# zulu_a7_2.net
KiCad netlist of a schematic drawn in Altium Designer
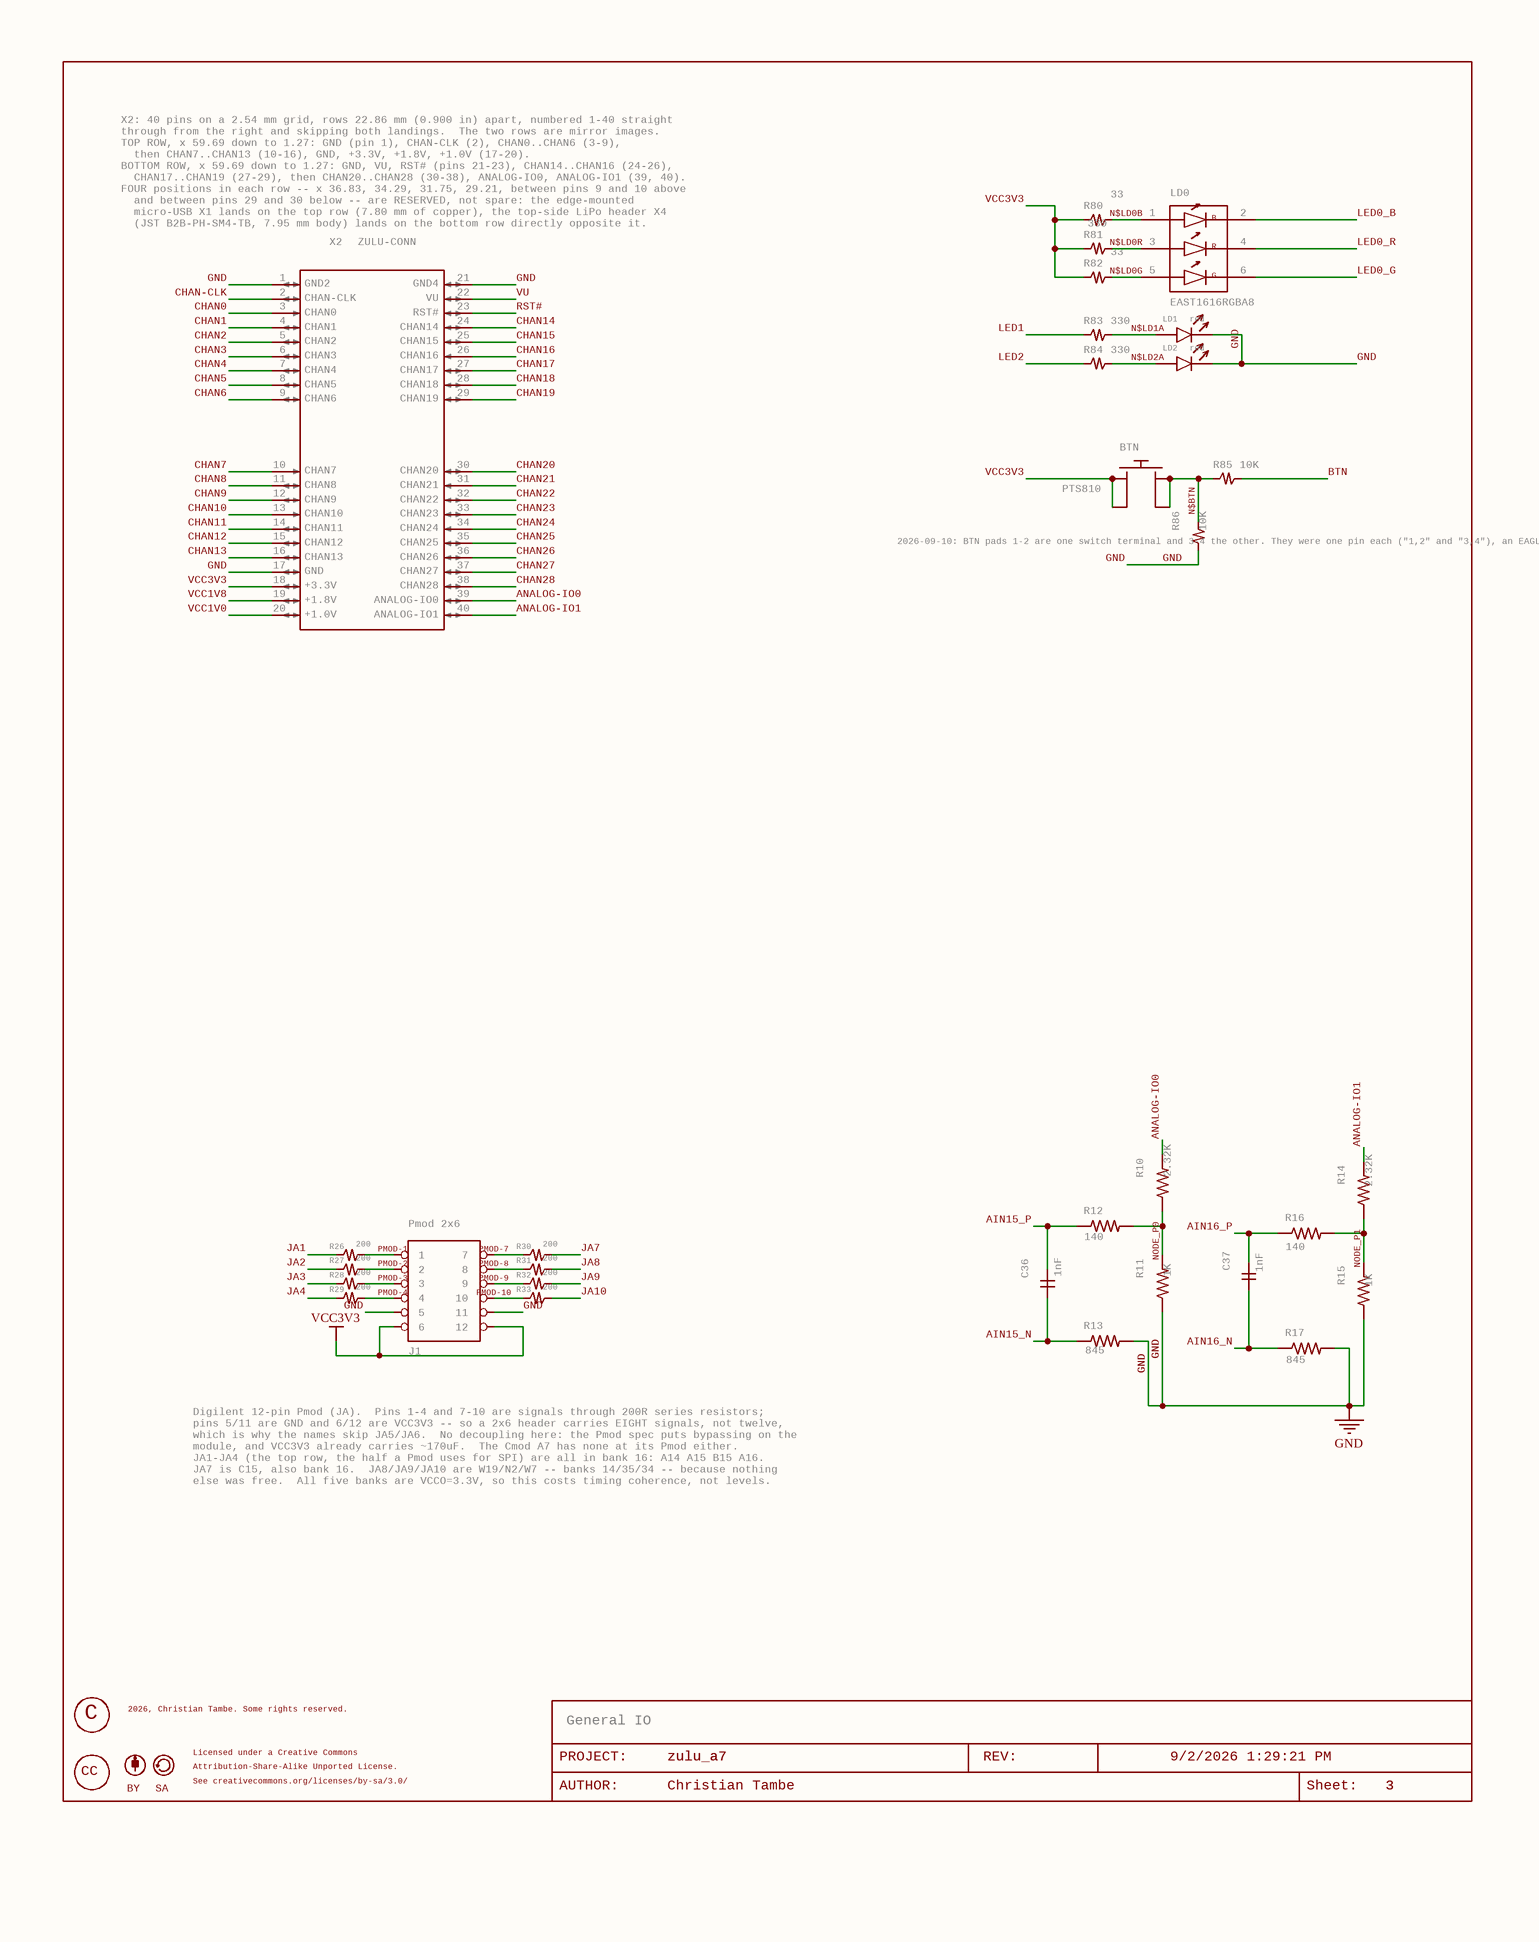
[diagram p0: zulu_a7_2.SchDoc]

(export (version "E")
  (design (tool "Eeschema 10.0.6"))
  (components
    (comp (ref "BTN")
      (value "PTS810")
      (footprint "PTS810")
      (fields (field (name "MANF") "Littelfuse (C&K)") (field (name "LIBRARYNAME") "ctambe"))
      (libsource (lib "ctambe") (part "SWITCH_TACT"))
    )
    (comp (ref "C36")
      (value "1nF")
      (footprint "C0402")
      (description "CAPACITOR, generic non-polarized, horizontal pins")
      (fields (field (name "MANF") "Murata"))
      (libsource (lib "rcl") (part "C-GENERICC0402"))
    )
    (comp (ref "C37")
      (value "1nF")
      (footprint "C0402")
      (description "CAPACITOR, generic non-polarized, horizontal pins")
      (fields (field (name "MANF") "Murata"))
      (libsource (lib "rcl") (part "C-GENERICC0402"))
    )
    (comp (ref "FRAME3")
      (value "DOCFIELD")
      (description "DOCUMENT FIELD")
      (fields
        (field (name "LAST_DATE_TIME") "9/2/2026 1:29:21 PM")
        (field (name "SHEET") "Sheet:")
        (field (name "SHEET_1") "3")
        (field (name "REV") "REV:")
        (field (name "PROJECT") "PROJECT:")
        (field (name "DRAWING_NAME") "zulu_a7")
        (field (name "AUTHOR") "Christian Tambe")
        (field (name "DRAWING_NAME_1") "zulu_a7")
        (field (name "SHEET_2") "3")
        (field (name "LIBRARYNAME") "ctambe")
      )
      (libsource (lib "ctambe") (part "DOCFIELD"))
    )
    (comp (ref "J1")
      (value "Pmod 2x6")
      (footprint "2X06")
      (fields (field (name "MANF") "Sullins") (field (name "LIBRARYNAME") "ctambe"))
      (libsource (lib "ctambe") (part "PINHD-2X6"))
    )
    (comp (ref "LD0")
      (value "EAST1616RGBA8")
      (footprint "EVERLIGHT-19-337")
      (fields
        (field (name "B") "B")
        (field (name "R") "R")
        (field (name "G") "G")
        (field (name "MANF") "Everlight")
        (field (name "LIBRARYNAME") "ctambe")
      )
      (libsource (lib "ctambe") (part "LED_RGB"))
    )
    (comp (ref "LD1")
      (value "red")
      (footprint "LED0603")
      (description "LED")
      (fields (field (name "MANF") "Lite-On") (field (name "LIBRARYNAME") "ctambe"))
      (libsource (lib "ctambe") (part "LED"))
    )
    (comp (ref "LD2")
      (value "red")
      (footprint "LED0603")
      (description "LED")
      (fields (field (name "MANF") "Lite-On") (field (name "LIBRARYNAME") "ctambe"))
      (libsource (lib "ctambe") (part "LED"))
    )
    (comp (ref "R10")
      (value "2.32K")
      (footprint "R0201")
      (description "RESISTOR, American symbol")
      (fields (field (name "MANF") "Yageo"))
      (libsource (lib "rcl") (part "R-US_R0201"))
    )
    (comp (ref "R11")
      (value "1K")
      (footprint "R0201")
      (description "RESISTOR, American symbol")
      (fields (field (name "MANF") "Yageo"))
      (libsource (lib "rcl") (part "R-US_R0201"))
    )
    (comp (ref "R12")
      (value "140")
      (footprint "R0201")
      (description "RESISTOR, American symbol")
      (fields (field (name "MANF") "Yageo"))
      (libsource (lib "rcl") (part "R-US_R0201"))
    )
    (comp (ref "R13")
      (value "845")
      (footprint "R0201")
      (description "RESISTOR, American symbol")
      (fields (field (name "MANF") "Yageo"))
      (libsource (lib "rcl") (part "R-US_R0201"))
    )
    (comp (ref "R14")
      (value "2.32K")
      (footprint "R0201")
      (description "RESISTOR, American symbol")
      (fields (field (name "MANF") "Yageo"))
      (libsource (lib "rcl") (part "R-US_R0201"))
    )
    (comp (ref "R15")
      (value "1K")
      (footprint "R0201")
      (description "RESISTOR, American symbol")
      (fields (field (name "MANF") "Yageo"))
      (libsource (lib "rcl") (part "R-US_R0201"))
    )
    (comp (ref "R16")
      (value "140")
      (footprint "R0201")
      (description "RESISTOR, American symbol")
      (fields (field (name "MANF") "Yageo"))
      (libsource (lib "rcl") (part "R-US_R0201"))
    )
    (comp (ref "R17")
      (value "845")
      (footprint "R0201")
      (description "RESISTOR, American symbol")
      (fields (field (name "MANF") "Yageo"))
      (libsource (lib "rcl") (part "R-US_R0201"))
    )
    (comp (ref "R26")
      (value "200")
      (footprint "R0201")
      (description "RESISTOR, American symbol, small 2-zigzag variant (sheet 2 only)")
      (fields (field (name "MANF") "Yageo"))
      (libsource (lib "rcl") (part "R-US_SMALLR0201"))
    )
    (comp (ref "R27")
      (value "200")
      (footprint "R0201")
      (description "RESISTOR, American symbol, small 2-zigzag variant (sheet 2 only)")
      (fields (field (name "MANF") "Yageo"))
      (libsource (lib "rcl") (part "R-US_SMALLR0201"))
    )
    (comp (ref "R28")
      (value "200")
      (footprint "R0201")
      (description "RESISTOR, American symbol, small 2-zigzag variant (sheet 2 only)")
      (fields (field (name "MANF") "Yageo"))
      (libsource (lib "rcl") (part "R-US_SMALLR0201"))
    )
    (comp (ref "R29")
      (value "200")
      (footprint "R0201")
      (description "RESISTOR, American symbol, small 2-zigzag variant (sheet 2 only)")
      (fields (field (name "MANF") "Yageo"))
      (libsource (lib "rcl") (part "R-US_SMALLR0201"))
    )
    (comp (ref "R30")
      (value "200")
      (footprint "R0201")
      (description "RESISTOR, American symbol, small 2-zigzag variant (sheet 2 only)")
      (fields (field (name "MANF") "Yageo"))
      (libsource (lib "rcl") (part "R-US_SMALLR0201"))
    )
    (comp (ref "R31")
      (value "200")
      (footprint "R0201")
      (description "RESISTOR, American symbol, small 2-zigzag variant (sheet 2 only)")
      (fields (field (name "MANF") "Yageo"))
      (libsource (lib "rcl") (part "R-US_SMALLR0201"))
    )
    (comp (ref "R32")
      (value "200")
      (footprint "R0201")
      (description "RESISTOR, American symbol, small 2-zigzag variant (sheet 2 only)")
      (fields (field (name "MANF") "Yageo"))
      (libsource (lib "rcl") (part "R-US_SMALLR0201"))
    )
    (comp (ref "R33")
      (value "200")
      (footprint "R0201")
      (description "RESISTOR, American symbol, small 2-zigzag variant (sheet 2 only)")
      (fields (field (name "MANF") "Yageo"))
      (libsource (lib "rcl") (part "R-US_SMALLR0201"))
    )
    (comp (ref "R80")
      (value "33")
      (footprint "R0402")
      (description "RESISTOR, American symbol, small 2-zigzag variant (sheet 2 only)")
      (fields (field (name "MANF") "Yageo"))
      (libsource (lib "rcl") (part "R-US_SMALLR0402"))
    )
    (comp (ref "R81")
      (value "330")
      (footprint "R0402")
      (description "RESISTOR, American symbol, small 2-zigzag variant (sheet 2 only)")
      (fields (field (name "MANF") "Yageo"))
      (libsource (lib "rcl") (part "R-US_SMALLR0402"))
    )
    (comp (ref "R82")
      (value "33")
      (footprint "R0402")
      (description "RESISTOR, American symbol, small 2-zigzag variant (sheet 2 only)")
      (fields (field (name "MANF") "Yageo"))
      (libsource (lib "rcl") (part "R-US_SMALLR0402"))
    )
    (comp (ref "R83")
      (value "330")
      (footprint "R0402")
      (description "RESISTOR, American symbol, small 2-zigzag variant (sheet 2 only)")
      (fields (field (name "MANF") "Yageo"))
      (libsource (lib "rcl") (part "R-US_SMALLR0402"))
    )
    (comp (ref "R84")
      (value "330")
      (footprint "R0402")
      (description "RESISTOR, American symbol, small 2-zigzag variant (sheet 2 only)")
      (fields (field (name "MANF") "Yageo"))
      (libsource (lib "rcl") (part "R-US_SMALLR0402"))
    )
    (comp (ref "R85")
      (value "10K")
      (footprint "R0402")
      (description "RESISTOR, American symbol, small 2-zigzag variant (sheet 2 only)")
      (fields (field (name "MANF") "Yageo"))
      (libsource (lib "rcl") (part "R-US_SMALLR0402"))
    )
    (comp (ref "R86")
      (value "10K")
      (footprint "R0402")
      (description "RESISTOR, American symbol, small 2-zigzag variant (sheet 2 only)")
      (fields (field (name "MANF") "Yageo"))
      (libsource (lib "rcl") (part "R-US_SMALLR0402"))
    )
    (comp (ref "U$2")
      (value "CC_CC")
      (footprint "CC_CC")
      (fields (field (name "CC") "CC") (field (name "LIBRARYNAME") "ctambe"))
      (libsource (lib "ctambe") (part "CC_CC"))
    )
    (comp (ref "U$3")
      (value "CC_BY")
      (footprint "CC_BY")
      (fields (field (name "BY") "BY") (field (name "LIBRARYNAME") "ctambe"))
      (libsource (lib "ctambe") (part "CC_BY"))
    )
    (comp (ref "U$4")
      (value "CC_SA")
      (footprint "CC_SA")
      (fields (field (name "SA") "SA") (field (name "LIBRARYNAME") "ctambe"))
      (libsource (lib "ctambe") (part "CC_SA"))
    )
    (comp (ref "U$5")
      (value "CC_COPYRIGHT")
      (footprint "CC_COPYRIGHT")
      (fields (field (name "C") "C") (field (name "LIBRARYNAME") "ctambe"))
      (libsource (lib "ctambe") (part "CC_COPYRIGHT"))
    )
    (comp (ref "X2")
      (value "ZULU-CONN")
      (footprint "ZULU-DIP37")
      (description "Zulu A7 Board Connector")
      (fields
        (field (name "MANF") "Sullins")
        (field (name "GATE") "CHAN-CLK")
        (field (name "PART") "X2")
        (field (name "LIBRARYNAME") "ctambe")
      )
      (libsource (lib "ctambe") (part "ZULU-CONN"))
    )
  )
  (nets
    (net (code "1") (name "/AIN15_N") (class "Default")
      (node (ref "C36") (pin "1") (pinfunction "1_1") (pintype "passive"))
      (node (ref "R13") (pin "1") (pinfunction "1_1") (pintype "passive"))
    )
    (net (code "2") (name "/AIN15_P") (class "Default")
      (node (ref "C36") (pin "2") (pinfunction "2_2") (pintype "passive"))
      (node (ref "R12") (pin "1") (pinfunction "1_1") (pintype "passive"))
    )
    (net (code "3") (name "/AIN16_N") (class "Default")
      (node (ref "C37") (pin "1") (pinfunction "1_1") (pintype "passive"))
      (node (ref "R17") (pin "1") (pinfunction "1_1") (pintype "passive"))
    )
    (net (code "4") (name "/AIN16_P") (class "Default")
      (node (ref "C37") (pin "2") (pinfunction "2_2") (pintype "passive"))
      (node (ref "R16") (pin "1") (pinfunction "1_1") (pintype "passive"))
    )
    (net (code "5") (name "/ANALOG-IO0") (class "Default")
      (node (ref "R10") (pin "2") (pinfunction "2_2") (pintype "passive"))
      (node (ref "X2") (pin "39") (pinfunction "1_39") (pintype "bidirectional"))
    )
    (net (code "6") (name "/ANALOG-IO1") (class "Default")
      (node (ref "R14") (pin "2") (pinfunction "2_2") (pintype "passive"))
      (node (ref "X2") (pin "40") (pinfunction "1_40") (pintype "bidirectional"))
    )
    (net (code "7") (name "/BTN") (class "Default")
      (node (ref "R85") (pin "2") (pinfunction "2_2") (pintype "passive"))
    )
    (net (code "8") (name "/CHAN-CLK") (class "Default")
      (node (ref "X2") (pin "2") (pinfunction "1_2") (pintype "bidirectional"))
    )
    (net (code "9") (name "/CHAN0") (class "Default")
      (node (ref "X2") (pin "3") (pinfunction "1_3") (pintype "input"))
    )
    (net (code "10") (name "/CHAN1") (class "Default")
      (node (ref "X2") (pin "4") (pinfunction "1_4") (pintype "bidirectional"))
    )
    (net (code "11") (name "/CHAN2") (class "Default")
      (node (ref "X2") (pin "5") (pinfunction "1_5") (pintype "bidirectional"))
    )
    (net (code "12") (name "/CHAN3") (class "Default")
      (node (ref "X2") (pin "6") (pinfunction "1_6") (pintype "bidirectional"))
    )
    (net (code "13") (name "/CHAN4") (class "Default")
      (node (ref "X2") (pin "7") (pinfunction "1_7") (pintype "bidirectional"))
    )
    (net (code "14") (name "/CHAN5") (class "Default")
      (node (ref "X2") (pin "8") (pinfunction "1_8") (pintype "bidirectional"))
    )
    (net (code "15") (name "/CHAN6") (class "Default")
      (node (ref "X2") (pin "9") (pinfunction "1_9") (pintype "bidirectional"))
    )
    (net (code "16") (name "/CHAN7") (class "Default")
      (node (ref "X2") (pin "10") (pinfunction "1_10") (pintype "input"))
    )
    (net (code "17") (name "/CHAN8") (class "Default")
      (node (ref "X2") (pin "11") (pinfunction "1_11") (pintype "passive"))
    )
    (net (code "18") (name "/CHAN9") (class "Default")
      (node (ref "X2") (pin "12") (pinfunction "1_12") (pintype "bidirectional"))
    )
    (net (code "19") (name "/CHAN10") (class "Default")
      (node (ref "X2") (pin "13") (pinfunction "1_13") (pintype "input"))
    )
    (net (code "20") (name "/CHAN11") (class "Default")
      (node (ref "X2") (pin "14") (pinfunction "1_14") (pintype "bidirectional"))
    )
    (net (code "21") (name "/CHAN12") (class "Default")
      (node (ref "X2") (pin "15") (pinfunction "1_15") (pintype "bidirectional"))
    )
    (net (code "22") (name "/CHAN13") (class "Default")
      (node (ref "X2") (pin "16") (pinfunction "1_16") (pintype "bidirectional"))
    )
    (net (code "23") (name "/CHAN14") (class "Default")
      (node (ref "X2") (pin "24") (pinfunction "1_24") (pintype "bidirectional"))
    )
    (net (code "24") (name "/CHAN15") (class "Default")
      (node (ref "X2") (pin "25") (pinfunction "1_25") (pintype "bidirectional"))
    )
    (net (code "25") (name "/CHAN16") (class "Default")
      (node (ref "X2") (pin "26") (pinfunction "1_26") (pintype "input"))
    )
    (net (code "26") (name "/CHAN17") (class "Default")
      (node (ref "X2") (pin "27") (pinfunction "1_27") (pintype "bidirectional"))
    )
    (net (code "27") (name "/CHAN18") (class "Default")
      (node (ref "X2") (pin "28") (pinfunction "1_28") (pintype "bidirectional"))
    )
    (net (code "28") (name "/CHAN19") (class "Default")
      (node (ref "X2") (pin "29") (pinfunction "1_29") (pintype "bidirectional"))
    )
    (net (code "29") (name "/CHAN20") (class "Default")
      (node (ref "X2") (pin "30") (pinfunction "1_30") (pintype "bidirectional"))
    )
    (net (code "30") (name "/CHAN21") (class "Default")
      (node (ref "X2") (pin "31") (pinfunction "1_31") (pintype "input"))
    )
    (net (code "31") (name "/CHAN22") (class "Default")
      (node (ref "X2") (pin "32") (pinfunction "1_32") (pintype "bidirectional"))
    )
    (net (code "32") (name "/CHAN23") (class "Default")
      (node (ref "X2") (pin "33") (pinfunction "1_33") (pintype "bidirectional"))
    )
    (net (code "33") (name "/CHAN24") (class "Default")
      (node (ref "X2") (pin "34") (pinfunction "1_34") (pintype "input"))
    )
    (net (code "34") (name "/CHAN25") (class "Default")
      (node (ref "X2") (pin "35") (pinfunction "1_35") (pintype "bidirectional"))
    )
    (net (code "35") (name "/CHAN26") (class "Default")
      (node (ref "X2") (pin "36") (pinfunction "1_36") (pintype "bidirectional"))
    )
    (net (code "36") (name "/CHAN27") (class "Default")
      (node (ref "X2") (pin "37") (pinfunction "1_37") (pintype "bidirectional"))
    )
    (net (code "37") (name "/CHAN28") (class "Default")
      (node (ref "X2") (pin "38") (pinfunction "1_38") (pintype "bidirectional"))
    )
    (net (code "38") (name "/JA1") (class "Default")
      (node (ref "R26") (pin "1") (pinfunction "1_1") (pintype "passive"))
    )
    (net (code "39") (name "/JA2") (class "Default")
      (node (ref "R27") (pin "1") (pinfunction "1_1") (pintype "passive"))
    )
    (net (code "40") (name "/JA3") (class "Default")
      (node (ref "R28") (pin "1") (pinfunction "1_1") (pintype "passive"))
    )
    (net (code "41") (name "/JA4") (class "Default")
      (node (ref "R29") (pin "1") (pinfunction "1_1") (pintype "passive"))
    )
    (net (code "42") (name "/JA7") (class "Default")
      (node (ref "R30") (pin "2") (pinfunction "2_2") (pintype "passive"))
    )
    (net (code "43") (name "/JA8") (class "Default")
      (node (ref "R31") (pin "2") (pinfunction "2_2") (pintype "passive"))
    )
    (net (code "44") (name "/JA9") (class "Default")
      (node (ref "R32") (pin "2") (pinfunction "2_2") (pintype "passive"))
    )
    (net (code "45") (name "/JA10") (class "Default")
      (node (ref "R33") (pin "2") (pinfunction "2_2") (pintype "passive"))
    )
    (net (code "46") (name "/LED0_B") (class "Default")
      (node (ref "LD0") (pin "2") (pinfunction "2_2") (pintype "passive"))
    )
    (net (code "47") (name "/LED0_G") (class "Default")
      (node (ref "LD0") (pin "6") (pinfunction "6_6") (pintype "passive"))
    )
    (net (code "48") (name "/LED0_R") (class "Default")
      (node (ref "LD0") (pin "4") (pinfunction "4_4") (pintype "passive"))
    )
    (net (code "49") (name "/LED1") (class "Default")
      (node (ref "R83") (pin "1") (pinfunction "1_1") (pintype "passive"))
    )
    (net (code "50") (name "/LED2") (class "Default")
      (node (ref "R84") (pin "1") (pinfunction "1_1") (pintype "passive"))
    )
    (net (code "51") (name "/N$BTN") (class "Default")
      (node (ref "BTN") (pin "3") (pinfunction "2_3") (pintype "passive"))
      (node (ref "BTN") (pin "4") (pinfunction "2_4") (pintype "passive"))
      (node (ref "R85") (pin "1") (pinfunction "1_1") (pintype "passive"))
      (node (ref "R86") (pin "2") (pinfunction "2_2") (pintype "passive"))
    )
    (net (code "52") (name "/N$LD0B") (class "Default")
      (node (ref "LD0") (pin "1") (pinfunction "1_1") (pintype "passive"))
      (node (ref "R80") (pin "2") (pinfunction "2_2") (pintype "passive"))
    )
    (net (code "53") (name "/N$LD0G") (class "Default")
      (node (ref "LD0") (pin "5") (pinfunction "5_5") (pintype "passive"))
      (node (ref "R82") (pin "2") (pinfunction "2_2") (pintype "passive"))
    )
    (net (code "54") (name "/N$LD0R") (class "Default")
      (node (ref "LD0") (pin "3") (pinfunction "3_3") (pintype "passive"))
      (node (ref "R81") (pin "2") (pinfunction "2_2") (pintype "passive"))
    )
    (net (code "55") (name "/N$LD1A") (class "Default")
      (node (ref "LD1") (pin "A") (pinfunction "A_A") (pintype "passive"))
      (node (ref "R83") (pin "2") (pinfunction "2_2") (pintype "passive"))
    )
    (net (code "56") (name "/N$LD2A") (class "Default")
      (node (ref "LD2") (pin "A") (pinfunction "A_A") (pintype "passive"))
      (node (ref "R84") (pin "2") (pinfunction "2_2") (pintype "passive"))
    )
    (net (code "57") (name "/NODE_P0") (class "Default")
      (node (ref "R10") (pin "1") (pinfunction "1_1") (pintype "passive"))
      (node (ref "R11") (pin "2") (pinfunction "2_2") (pintype "passive"))
      (node (ref "R12") (pin "2") (pinfunction "2_2") (pintype "passive"))
    )
    (net (code "58") (name "/NODE_P1") (class "Default")
      (node (ref "R14") (pin "1") (pinfunction "1_1") (pintype "passive"))
      (node (ref "R15") (pin "2") (pinfunction "2_2") (pintype "passive"))
      (node (ref "R16") (pin "2") (pinfunction "2_2") (pintype "passive"))
    )
    (net (code "59") (name "/PMOD-1") (class "Default")
      (node (ref "J1") (pin "1") (pinfunction "1_1") (pintype "passive"))
      (node (ref "R26") (pin "2") (pinfunction "2_2") (pintype "passive"))
    )
    (net (code "60") (name "/PMOD-2") (class "Default")
      (node (ref "J1") (pin "2") (pinfunction "2_2") (pintype "passive"))
      (node (ref "R27") (pin "2") (pinfunction "2_2") (pintype "passive"))
    )
    (net (code "61") (name "/PMOD-3") (class "Default")
      (node (ref "J1") (pin "3") (pinfunction "3_3") (pintype "passive"))
      (node (ref "R28") (pin "2") (pinfunction "2_2") (pintype "passive"))
    )
    (net (code "62") (name "/PMOD-4") (class "Default")
      (node (ref "J1") (pin "4") (pinfunction "4_4") (pintype "passive"))
      (node (ref "R29") (pin "2") (pinfunction "2_2") (pintype "passive"))
    )
    (net (code "63") (name "/PMOD-7") (class "Default")
      (node (ref "J1") (pin "7") (pinfunction "7_7") (pintype "passive"))
      (node (ref "R30") (pin "1") (pinfunction "1_1") (pintype "passive"))
    )
    (net (code "64") (name "/PMOD-8") (class "Default")
      (node (ref "J1") (pin "8") (pinfunction "8_8") (pintype "passive"))
      (node (ref "R31") (pin "1") (pinfunction "1_1") (pintype "passive"))
    )
    (net (code "65") (name "/PMOD-9") (class "Default")
      (node (ref "J1") (pin "9") (pinfunction "9_9") (pintype "passive"))
      (node (ref "R32") (pin "1") (pinfunction "1_1") (pintype "passive"))
    )
    (net (code "66") (name "/PMOD-10") (class "Default")
      (node (ref "J1") (pin "10") (pinfunction "10_10") (pintype "passive"))
      (node (ref "R33") (pin "1") (pinfunction "1_1") (pintype "passive"))
    )
    (net (code "67") (name "/RST#") (class "Default")
      (node (ref "X2") (pin "23") (pinfunction "1_23") (pintype "bidirectional"))
    )
    (net (code "68") (name "/VCC1V0") (class "Default")
      (node (ref "X2") (pin "20") (pinfunction "1_20") (pintype "bidirectional"))
    )
    (net (code "69") (name "/VCC1V8") (class "Default")
      (node (ref "X2") (pin "19") (pinfunction "1_19") (pintype "bidirectional"))
    )
    (net (code "70") (name "/VU") (class "Default")
      (node (ref "X2") (pin "22") (pinfunction "1_22") (pintype "bidirectional"))
    )
    (net (code "71") (name "GND") (class "Default")
      (node (ref "J1") (pin "11") (pinfunction "11_11") (pintype "passive"))
      (node (ref "J1") (pin "5") (pinfunction "5_5") (pintype "passive"))
      (node (ref "LD1") (pin "K") (pinfunction "K_K") (pintype "passive"))
      (node (ref "LD2") (pin "K") (pinfunction "K_K") (pintype "passive"))
      (node (ref "R11") (pin "1") (pinfunction "1_1") (pintype "passive"))
      (node (ref "R13") (pin "2") (pinfunction "2_2") (pintype "passive"))
      (node (ref "R15") (pin "1") (pinfunction "1_1") (pintype "passive"))
      (node (ref "R17") (pin "2") (pinfunction "2_2") (pintype "passive"))
      (node (ref "R86") (pin "1") (pinfunction "1_1") (pintype "passive"))
      (node (ref "X2") (pin "1") (pinfunction "1_1") (pintype "bidirectional"))
      (node (ref "X2") (pin "17") (pinfunction "1_17") (pintype "bidirectional"))
      (node (ref "X2") (pin "21") (pinfunction "1_21") (pintype "bidirectional"))
    )
    (net (code "72") (name "VCC3V3") (class "Default")
      (node (ref "BTN") (pin "1") (pinfunction "1_1") (pintype "passive"))
      (node (ref "BTN") (pin "2") (pinfunction "1_2") (pintype "passive"))
      (node (ref "J1") (pin "12") (pinfunction "12_12") (pintype "passive"))
      (node (ref "J1") (pin "6") (pinfunction "6_6") (pintype "passive"))
      (node (ref "R80") (pin "1") (pinfunction "1_1") (pintype "passive"))
      (node (ref "R81") (pin "1") (pinfunction "1_1") (pintype "passive"))
      (node (ref "R82") (pin "1") (pinfunction "1_1") (pintype "passive"))
      (node (ref "X2") (pin "18") (pinfunction "1_18") (pintype "bidirectional"))
    )
  )
)
